# Larson_Scanner.net
KiCad netlist of a schematic drawn in EAGLE
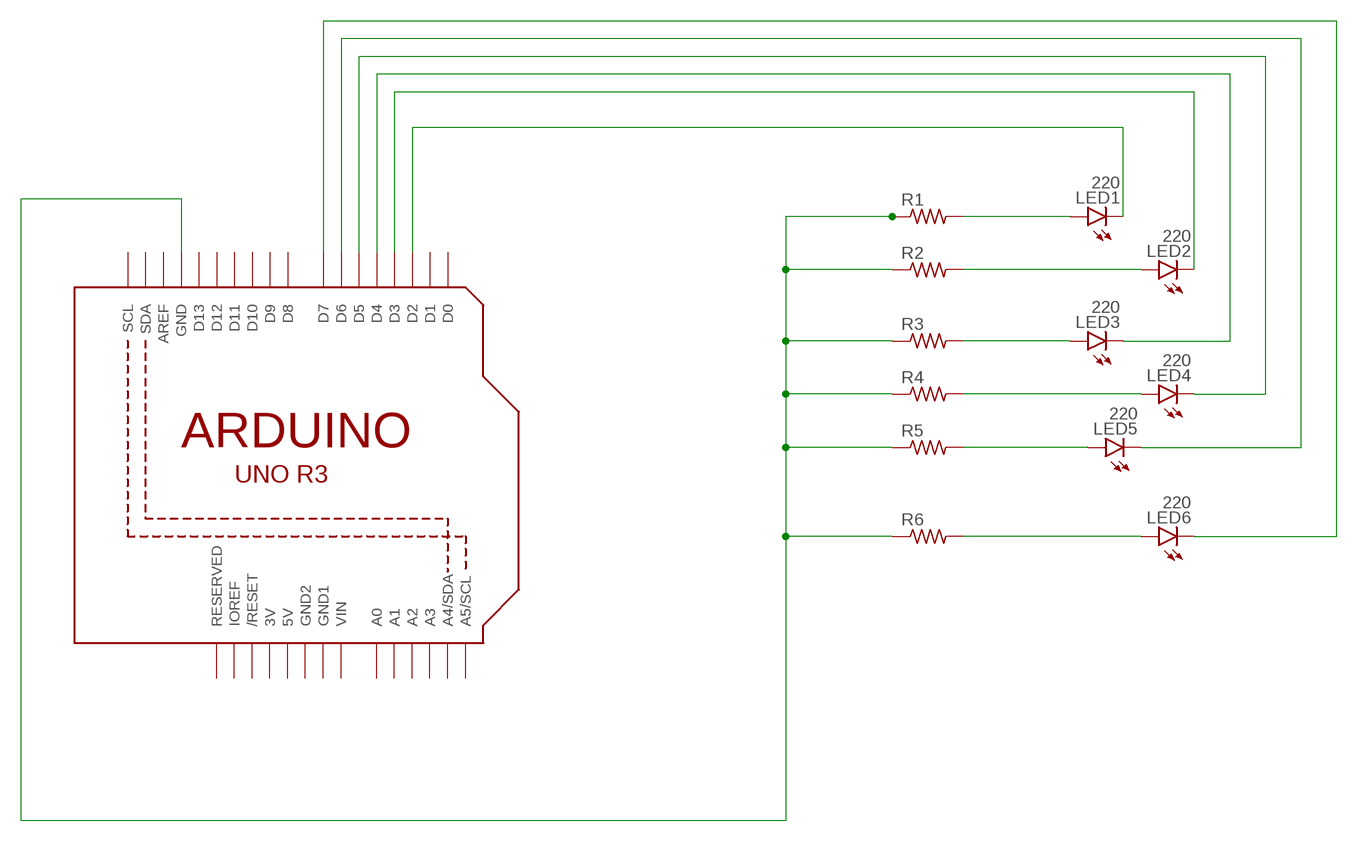
[diagram p0: schematic, sheet 1]

(export (version "E")
  (design (tool "Eeschema 10.0.6"))
  (components
    (comp (ref "LED1")
      (value "220")
      (footprint "eagle-import:SMARTLED-TTW")
      (libsource (lib "eagle-import") (part "LED"))
    )
    (comp (ref "LED2")
      (value "220")
      (footprint "eagle-import:SMARTLED-TTW")
      (libsource (lib "eagle-import") (part "LED"))
    )
    (comp (ref "LED3")
      (value "220")
      (footprint "eagle-import:SMARTLED-TTW")
      (libsource (lib "eagle-import") (part "LED"))
    )
    (comp (ref "LED4")
      (value "220")
      (footprint "eagle-import:SMARTLED-TTW")
      (libsource (lib "eagle-import") (part "LED"))
    )
    (comp (ref "LED5")
      (value "220")
      (footprint "eagle-import:SMARTLED-TTW")
      (libsource (lib "eagle-import") (part "LED"))
    )
    (comp (ref "LED6")
      (value "220")
      (footprint "eagle-import:SMARTLED-TTW")
      (libsource (lib "eagle-import") (part "LED"))
    )
    (comp (ref "R1")
      (value "R-US_R0603")
      (footprint "eagle-import:R0603")
      (libsource (lib "eagle-import") (part "R-US_R0603"))
    )
    (comp (ref "R2")
      (value "R-US_R0603")
      (footprint "eagle-import:R0603")
      (libsource (lib "eagle-import") (part "R-US_R0603"))
    )
    (comp (ref "R3")
      (value "R-US_R0603")
      (footprint "eagle-import:R0603")
      (libsource (lib "eagle-import") (part "R-US_R0603"))
    )
    (comp (ref "R4")
      (value "R-US_R0603")
      (footprint "eagle-import:R0603")
      (libsource (lib "eagle-import") (part "R-US_R0603"))
    )
    (comp (ref "R5")
      (value "R-US_R0603")
      (footprint "eagle-import:R0603")
      (libsource (lib "eagle-import") (part "R-US_R0603"))
    )
    (comp (ref "R6")
      (value "R-US_R0603")
      (footprint "eagle-import:R0603")
      (libsource (lib "eagle-import") (part "R-US_R0603"))
    )
    (comp (ref "U1")
      (value "ARDUINOR3-DIMENSION")
      (footprint "eagle-import:ARDUINOR3")
      (libsource (lib "eagle-import") (part "ARDUINOR3-DIMENSION"))
    )
  )
  (nets
    (net (code "1") (name "/3V") (class "Default")
      (node (ref "U1") (pin "3V") (pinfunction "3V_3V") (pintype "power_in"))
    )
    (net (code "2") (name "/5V") (class "Default")
      (node (ref "U1") (pin "5V") (pinfunction "5V_5V") (pintype "power_in"))
    )
    (net (code "3") (name "/GND1") (class "Default")
      (node (ref "U1") (pin "GND1") (pinfunction "GND1_GND1") (pintype "power_in"))
    )
    (net (code "4") (name "/GND2") (class "Default")
      (node (ref "U1") (pin "GND2") (pinfunction "GND2_GND2") (pintype "power_in"))
    )
    (net (code "5") (name "/VIN") (class "Default")
      (node (ref "U1") (pin "VIN") (pinfunction "VIN_VIN") (pintype "power_in"))
    )
    (net (code "6") (name "Net-(LED1-A)") (class "Default")
      (node (ref "LED1") (pin "A@1") (pinfunction "A_A@1") (pintype "passive"))
      (node (ref "R1") (pin "2") (pinfunction "2_2") (pintype "passive"))
    )
    (net (code "7") (name "Net-(LED1-C)") (class "Default")
      (node (ref "LED1") (pin "C@1") (pinfunction "C_C@1") (pintype "passive"))
      (node (ref "U1") (pin "D2") (pinfunction "D2_D2") (pintype "bidirectional"))
    )
    (net (code "8") (name "Net-(LED2-A)") (class "Default")
      (node (ref "LED2") (pin "A@1") (pinfunction "A_A@1") (pintype "passive"))
      (node (ref "R2") (pin "2") (pinfunction "2_2") (pintype "passive"))
    )
    (net (code "9") (name "Net-(LED2-C)") (class "Default")
      (node (ref "LED2") (pin "C@1") (pinfunction "C_C@1") (pintype "passive"))
      (node (ref "U1") (pin "D3") (pinfunction "D3_D3") (pintype "bidirectional"))
    )
    (net (code "10") (name "Net-(LED3-A)") (class "Default")
      (node (ref "LED3") (pin "A@1") (pinfunction "A_A@1") (pintype "passive"))
      (node (ref "R3") (pin "2") (pinfunction "2_2") (pintype "passive"))
    )
    (net (code "11") (name "Net-(LED3-C)") (class "Default")
      (node (ref "LED3") (pin "C@1") (pinfunction "C_C@1") (pintype "passive"))
      (node (ref "U1") (pin "D4") (pinfunction "D4_D4") (pintype "bidirectional"))
    )
    (net (code "12") (name "Net-(LED4-A)") (class "Default")
      (node (ref "LED4") (pin "A@1") (pinfunction "A_A@1") (pintype "passive"))
      (node (ref "R4") (pin "2") (pinfunction "2_2") (pintype "passive"))
    )
    (net (code "13") (name "Net-(LED4-C)") (class "Default")
      (node (ref "LED4") (pin "C@1") (pinfunction "C_C@1") (pintype "passive"))
      (node (ref "U1") (pin "D5") (pinfunction "D5_D5") (pintype "bidirectional"))
    )
    (net (code "14") (name "Net-(LED5-A)") (class "Default")
      (node (ref "LED5") (pin "A@1") (pinfunction "A_A@1") (pintype "passive"))
      (node (ref "R5") (pin "2") (pinfunction "2_2") (pintype "passive"))
    )
    (net (code "15") (name "Net-(LED5-C)") (class "Default")
      (node (ref "LED5") (pin "C@1") (pinfunction "C_C@1") (pintype "passive"))
      (node (ref "U1") (pin "D6") (pinfunction "D6_D6") (pintype "bidirectional"))
    )
    (net (code "16") (name "Net-(LED6-A)") (class "Default")
      (node (ref "LED6") (pin "A@1") (pinfunction "A_A@1") (pintype "passive"))
      (node (ref "R6") (pin "2") (pinfunction "2_2") (pintype "passive"))
    )
    (net (code "17") (name "Net-(LED6-C)") (class "Default")
      (node (ref "LED6") (pin "C@1") (pinfunction "C_C@1") (pintype "passive"))
      (node (ref "U1") (pin "D7") (pinfunction "D7_D7") (pintype "bidirectional"))
    )
    (net (code "18") (name "Net-(R1-Pad1)") (class "Default")
      (node (ref "R1") (pin "1") (pinfunction "1_1") (pintype "passive"))
      (node (ref "R2") (pin "1") (pinfunction "1_1") (pintype "passive"))
      (node (ref "R3") (pin "1") (pinfunction "1_1") (pintype "passive"))
      (node (ref "R4") (pin "1") (pinfunction "1_1") (pintype "passive"))
      (node (ref "R5") (pin "1") (pinfunction "1_1") (pintype "passive"))
      (node (ref "R6") (pin "1") (pinfunction "1_1") (pintype "passive"))
      (node (ref "U1") (pin "GND") (pinfunction "GND_GND") (pintype "power_in"))
    )
    (net (code "19") (name "unconnected-(U1-A4{slash}SDA-PadA4)") (class "Default")
      (node (ref "U1") (pin "A4") (pinfunction "A4/SDA_A4") (pintype "bidirectional"))
    )
    (net (code "20") (name "unconnected-(U1-A5{slash}SCL-PadA5)") (class "Default")
      (node (ref "U1") (pin "A5") (pinfunction "A5/SCL_A5") (pintype "bidirectional"))
    )
    (net (code "21") (name "unconnected-(U1-PadA0)") (class "Default")
      (node (ref "U1") (pin "A0") (pinfunction "A0_A0") (pintype "bidirectional"))
    )
    (net (code "22") (name "unconnected-(U1-PadA1)") (class "Default")
      (node (ref "U1") (pin "A1") (pinfunction "A1_A1") (pintype "bidirectional"))
    )
    (net (code "23") (name "unconnected-(U1-PadA2)") (class "Default")
      (node (ref "U1") (pin "A2") (pinfunction "A2_A2") (pintype "bidirectional"))
    )
    (net (code "24") (name "unconnected-(U1-PadA3)") (class "Default")
      (node (ref "U1") (pin "A3") (pinfunction "A3_A3") (pintype "bidirectional"))
    )
    (net (code "25") (name "unconnected-(U1-PadAREF)") (class "Default")
      (node (ref "U1") (pin "AREF") (pinfunction "AREF_AREF") (pintype "bidirectional"))
    )
    (net (code "26") (name "unconnected-(U1-PadD0)") (class "Default")
      (node (ref "U1") (pin "D0") (pinfunction "D0_D0") (pintype "bidirectional"))
    )
    (net (code "27") (name "unconnected-(U1-PadD1)") (class "Default")
      (node (ref "U1") (pin "D1") (pinfunction "D1_D1") (pintype "bidirectional"))
    )
    (net (code "28") (name "unconnected-(U1-PadD8)") (class "Default")
      (node (ref "U1") (pin "D8") (pinfunction "D8_D8") (pintype "bidirectional"))
    )
    (net (code "29") (name "unconnected-(U1-PadD9)") (class "Default")
      (node (ref "U1") (pin "D9") (pinfunction "D9_D9") (pintype "bidirectional"))
    )
    (net (code "30") (name "unconnected-(U1-PadD10)") (class "Default")
      (node (ref "U1") (pin "D10") (pinfunction "D10_D10") (pintype "bidirectional"))
    )
    (net (code "31") (name "unconnected-(U1-PadD11)") (class "Default")
      (node (ref "U1") (pin "D11") (pinfunction "D11_D11") (pintype "bidirectional"))
    )
    (net (code "32") (name "unconnected-(U1-PadD12)") (class "Default")
      (node (ref "U1") (pin "D12") (pinfunction "D12_D12") (pintype "bidirectional"))
    )
    (net (code "33") (name "unconnected-(U1-PadD13)") (class "Default")
      (node (ref "U1") (pin "D13") (pinfunction "D13_D13") (pintype "bidirectional"))
    )
    (net (code "34") (name "unconnected-(U1-PadIOREF)") (class "Default")
      (node (ref "U1") (pin "IOREF") (pinfunction "IOREF_IOREF") (pintype "output"))
    )
    (net (code "35") (name "unconnected-(U1-PadRESERVED)") (class "Default")
      (node (ref "U1") (pin "RESERVED") (pinfunction "RESERVED_RESERVED") (pintype "no_connect"))
    )
    (net (code "36") (name "unconnected-(U1-PadSCL)") (class "Default")
      (node (ref "U1") (pin "SCL") (pinfunction "SCL_SCL") (pintype "bidirectional"))
    )
    (net (code "37") (name "unconnected-(U1-PadSDA)") (class "Default")
      (node (ref "U1") (pin "SDA") (pinfunction "SDA_SDA") (pintype "bidirectional"))
    )
    (net (code "38") (name "unconnected-(U1-{slash}RESET-PadRESET)") (class "Default")
      (node (ref "U1") (pin "RESET") (pinfunction "/RESET_RESET") (pintype "bidirectional"))
    )
  )
)
